# obc-v2_CM4-M2.net
KiCad netlist of a schematic drawn in Altium Designer
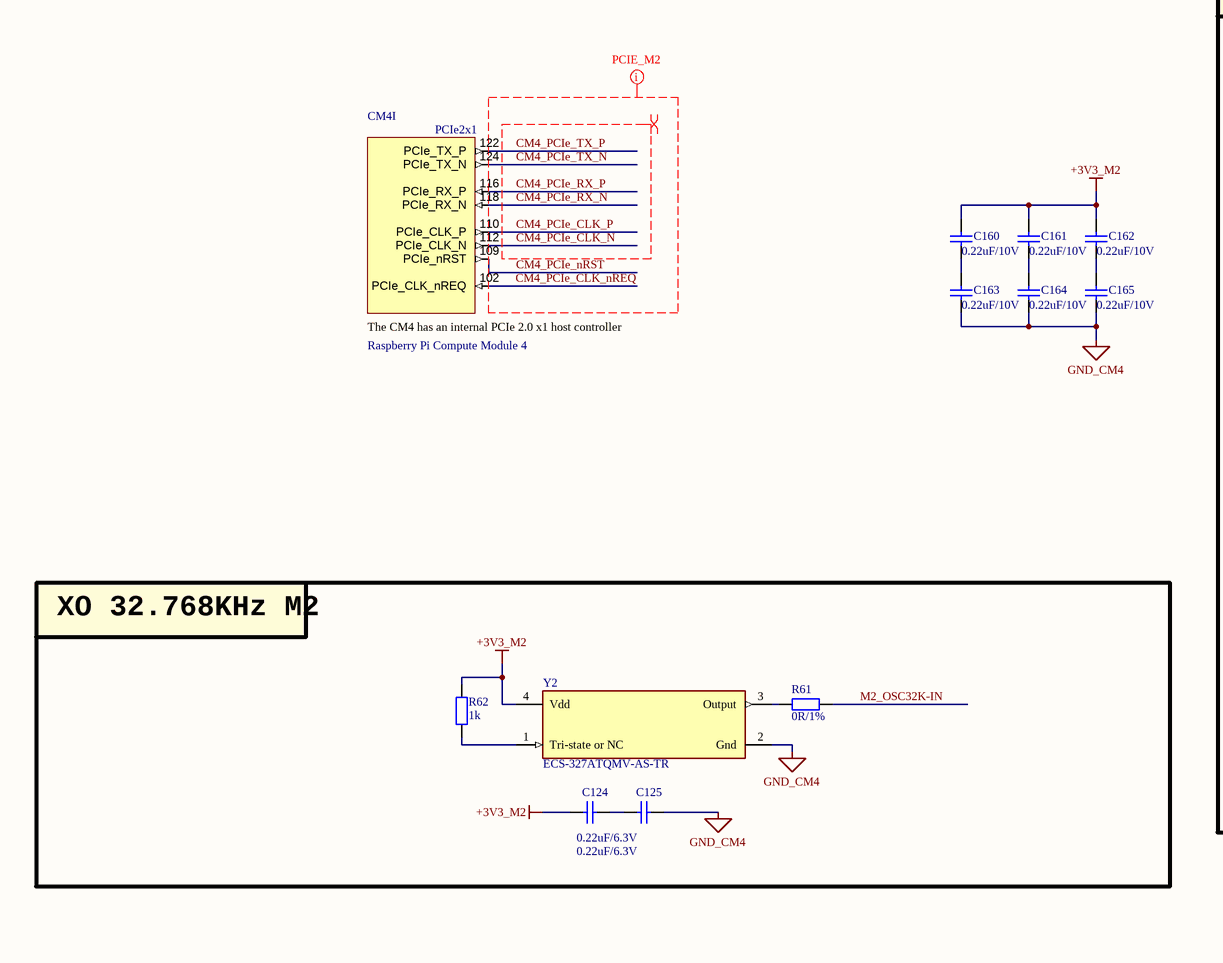
[diagram p0: obc-v2_CM4-M2.SchDoc, left]
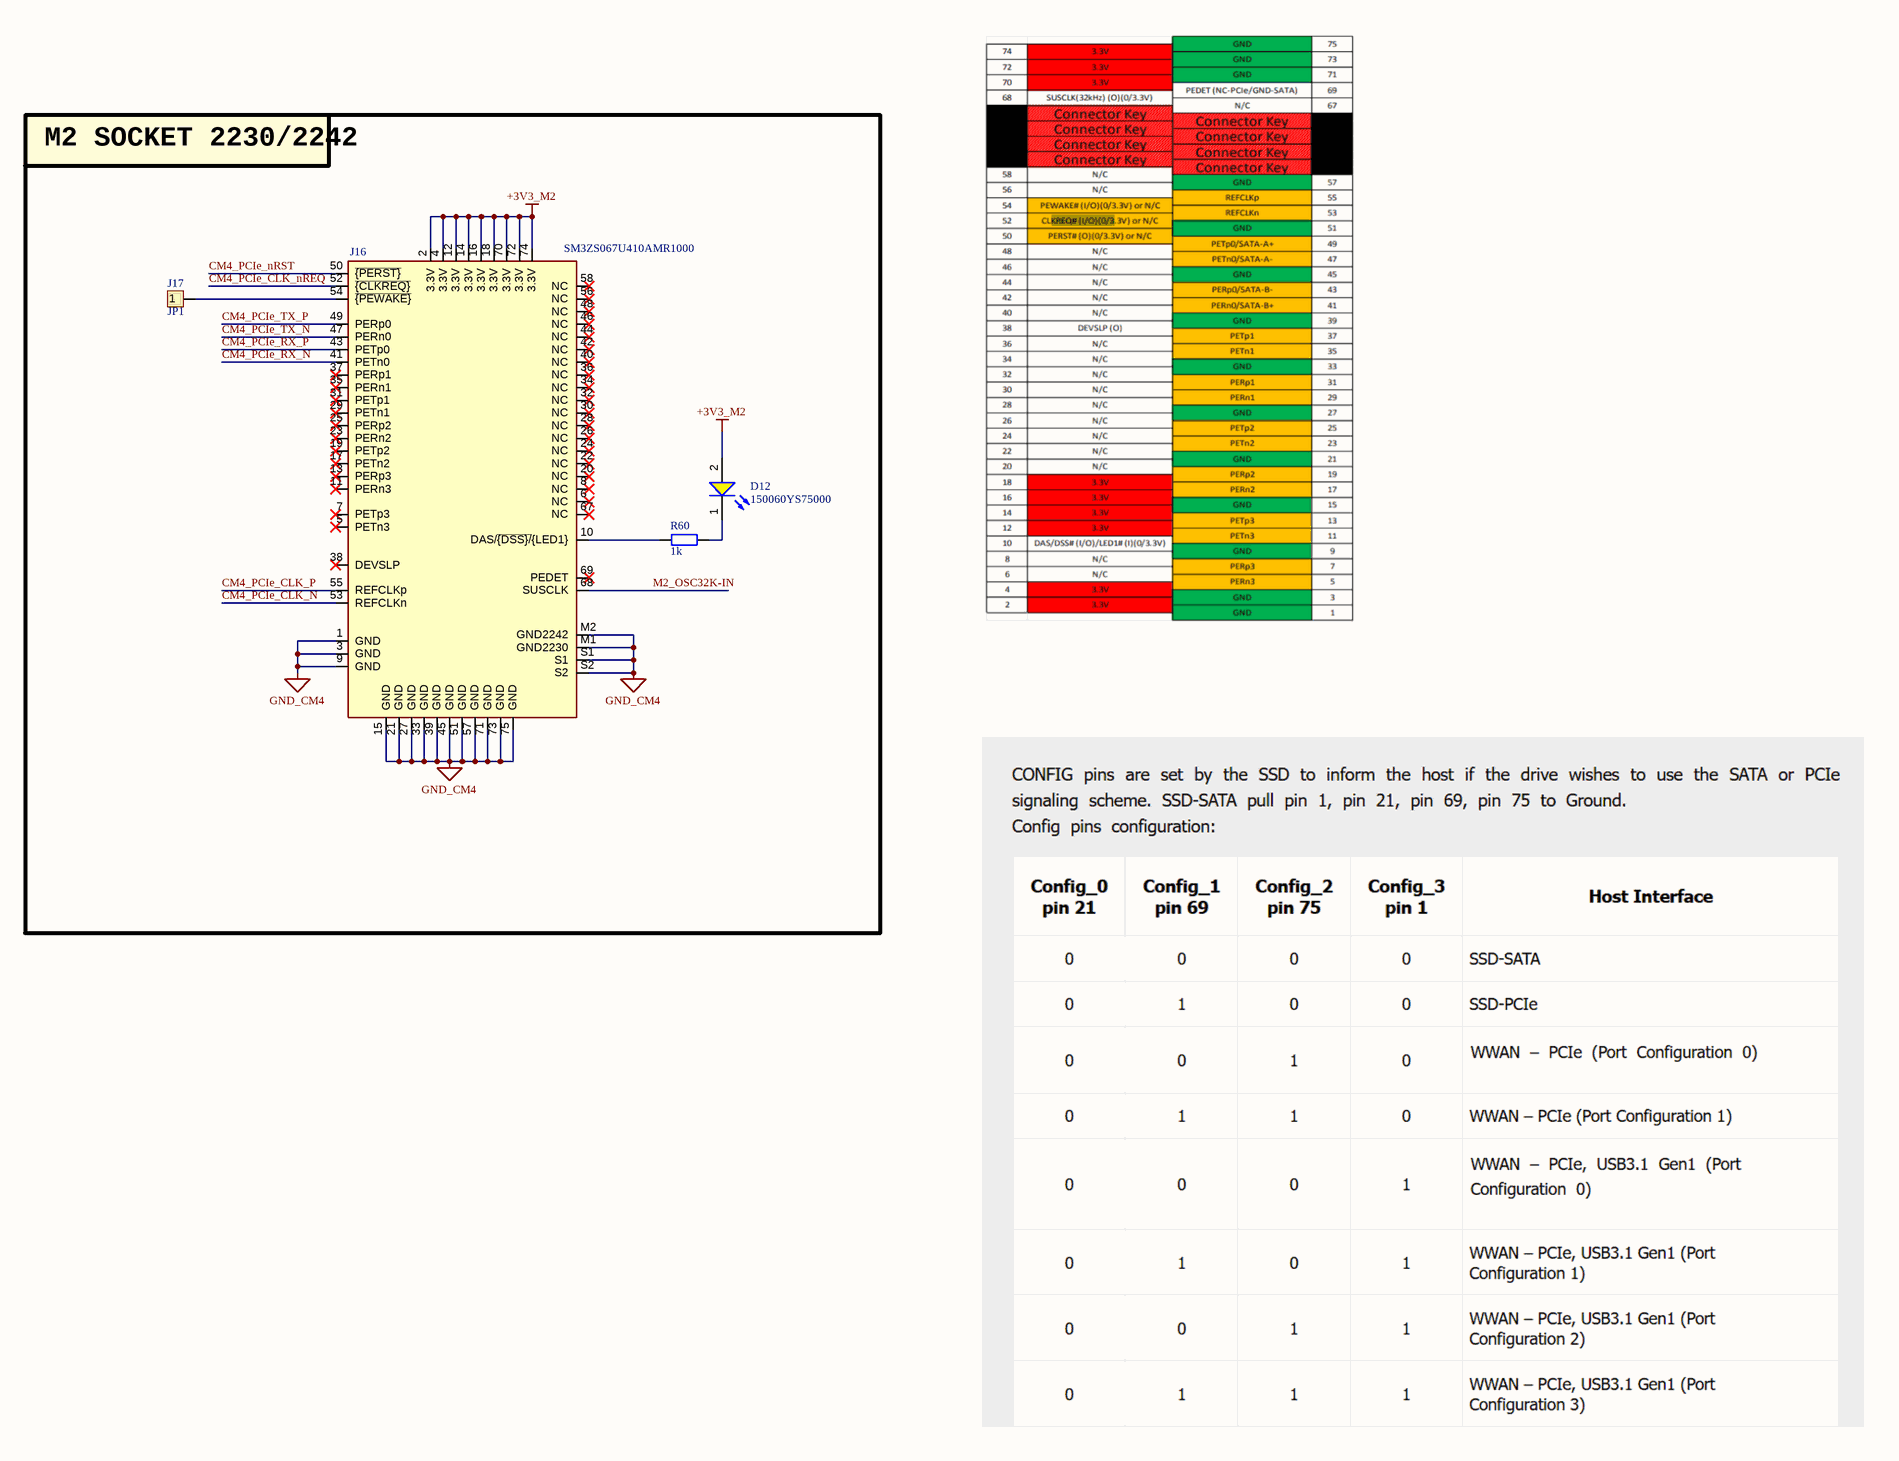
[diagram p1: obc-v2_CM4-M2.SchDoc, right]

(export (version "E")
  (design (tool "Eeschema 10.0.6"))
  (components
    (comp (ref "C124")
      (value "0.22uF/6.3V")
      (footprint "CAP_C_1005X60")
      (description "CAPC")
      (libsource (lib "Altium_Lib_by_KhueNguyenCreator") (part "Tu 0402 33nF 10V"))
    )
    (comp (ref "C125")
      (value "0.22uF/6.3V")
      (footprint "CAP_C_1005X60")
      (description "CAPC")
      (libsource (lib "Altium_Lib_by_KhueNguyenCreator") (part "Tu 0402 33nF 10V"))
    )
    (comp (ref "C160")
      (value "0.22uF/10V")
      (footprint "CAP_C_1005X60")
      (description "CAPC")
      (libsource (lib "Altium_Lib_by_KhueNguyenCreator") (part "Tu 0402 33nF 10V"))
    )
    (comp (ref "C161")
      (value "0.22uF/10V")
      (footprint "CAP_C_1005X60")
      (description "CAPC")
      (libsource (lib "Altium_Lib_by_KhueNguyenCreator") (part "Tu 0402 33nF 10V"))
    )
    (comp (ref "C162")
      (value "0.22uF/10V")
      (footprint "CAP_C_1005X60")
      (description "CAPC")
      (libsource (lib "Altium_Lib_by_KhueNguyenCreator") (part "Tu 0402 33nF 10V"))
    )
    (comp (ref "C163")
      (value "0.22uF/10V")
      (footprint "CAP_C_1005X60")
      (description "CAPC")
      (libsource (lib "Altium_Lib_by_KhueNguyenCreator") (part "Tu 0402 33nF 10V"))
    )
    (comp (ref "C164")
      (value "0.22uF/10V")
      (footprint "CAP_C_1005X60")
      (description "CAPC")
      (libsource (lib "Altium_Lib_by_KhueNguyenCreator") (part "Tu 0402 33nF 10V"))
    )
    (comp (ref "C165")
      (value "0.22uF/10V")
      (footprint "CAP_C_1005X60")
      (description "CAPC")
      (libsource (lib "Altium_Lib_by_KhueNguyenCreator") (part "Tu 0402 33nF 10V"))
    )
    (comp (ref "CM4")
      (value "Raspberry Pi Compute Module 4")
      (footprint "CM4-DF40HC(3.0)-100DS-0.4v_3mm_1.5mm")
      (description "Raspberry Pi Compute Module 4 by Amornthep Phunsin")
      (libsource (lib "CM4") (part "CM4"))
    )
    (comp (ref "D12")
      (value "150060YS75000")
      (footprint "WL-SMCW_0603_150060xx75000")
      (description "LED YELLOW CLEAR 0603 SMD")
      (libsource (lib "Altium Content Vault") (part "LED_Yellow_2A-1K"))
    )
    (comp (ref "J16")
      (value "SM3ZS067U410AMR1000")
      (footprint "M.2 M Key socket")
      (fields (field (name "Comment") "Bus_M.2_Socket_M"))
      (libsource (lib "CM5_GPIO") (part "Bus_M.2_Socket_M"))
    )
    (comp (ref "J17")
      (value "JP1")
      (footprint "JP1-D1T")
      (description "WR-PHD 2.54 mm Angled Socket Header")
      (fields
        (field (name "MANUFACTURER") "Würth Elektronik eiSos GmbH")
        (field (name "PARTNO") "613002143121")
        (field (name "CREATED BY") "Karrer Zheng")
      )
      (libsource (lib "TechMT.VN_Lib_Project v2") (part "JP1"))
    )
    (comp (ref "R60")
      (value "1k")
      (footprint "RES_C_1608X60")
      (description "RES")
      (libsource (lib "Altium_Lib_by_KhueNguyenCreator") (part "Tro 0603 1% 10k"))
    )
    (comp (ref "R61")
      (value "0R/1%")
      (footprint "RES_C_1608X60")
      (description "RES")
      (libsource (lib "Altium_Lib_by_KhueNguyenCreator") (part "Tro 0603 1% 10k"))
    )
    (comp (ref "R62")
      (value "1k")
      (footprint "RES_C_1608X60")
      (description "RES")
      (libsource (lib "Altium_Lib_by_KhueNguyenCreator") (part "Tro 0603 1% 10k"))
    )
    (comp (ref "Y2")
      (value "ECS-327ATQMV-AS-TR")
      (footprint "FP-327ATQMV-MFG")
      (description "XTAL OSC XO 32.7680KHZ CMOS SMD")
      (libsource (lib "Altium Content Vault") (part "48575ee33648fc99c8f9879a7ebcfb2"))
    )
  )
  (nets
    (net (code "1") (name "+3V3_M2") (class "Default")
      (node (ref "C124") (pin "1") (pinfunction "1_1") (pintype "passive"))
      (node (ref "C160") (pin "1") (pinfunction "1_1") (pintype "passive"))
      (node (ref "C161") (pin "1") (pinfunction "1_1") (pintype "passive"))
      (node (ref "C162") (pin "1") (pinfunction "1_1") (pintype "passive"))
      (node (ref "D12") (pin "2") (pinfunction "A_2") (pintype "passive"))
      (node (ref "J16") (pin "12") (pinfunction "3.3V_12") (pintype "passive"))
      (node (ref "J16") (pin "14") (pinfunction "3.3V_14") (pintype "passive"))
      (node (ref "J16") (pin "16") (pinfunction "3.3V_16") (pintype "passive"))
      (node (ref "J16") (pin "18") (pinfunction "3.3V_18") (pintype "passive"))
      (node (ref "J16") (pin "2") (pinfunction "3.3V_2") (pintype "passive"))
      (node (ref "J16") (pin "4") (pinfunction "3.3V_4") (pintype "passive"))
      (node (ref "J16") (pin "70") (pinfunction "3.3V_70") (pintype "passive"))
      (node (ref "J16") (pin "72") (pinfunction "3.3V_72") (pintype "passive"))
      (node (ref "J16") (pin "74") (pinfunction "3.3V_74") (pintype "passive"))
      (node (ref "R62") (pin "1") (pinfunction "1_1") (pintype "passive"))
      (node (ref "Y2") (pin "4") (pinfunction "Vdd_4") (pintype "power_in"))
    )
    (net (code "2") (name "/CM4_PCIe_CLK_N") (class "Default")
      (node (ref "CM4") (pin "112") (pinfunction "PCIe_CLK_N_112") (pintype "output"))
      (node (ref "J16") (pin "53") (pinfunction "REFCLKn_53") (pintype "passive"))
    )
    (net (code "3") (name "/CM4_PCIe_CLK_P") (class "Default")
      (node (ref "CM4") (pin "110") (pinfunction "PCIe_CLK_P_110") (pintype "output"))
      (node (ref "J16") (pin "55") (pinfunction "REFCLKp_55") (pintype "passive"))
    )
    (net (code "4") (name "/CM4_PCIe_CLK_nREQ") (class "Default")
      (node (ref "CM4") (pin "102") (pinfunction "PCIe_CLK_nREQ_102") (pintype "input"))
      (node (ref "J16") (pin "52") (pinfunction "~{{CLKREQ}}_52") (pintype "passive"))
    )
    (net (code "5") (name "/CM4_PCIe_RX_N") (class "Default")
      (node (ref "CM4") (pin "118") (pinfunction "PCIe_RX_N_118") (pintype "input"))
      (node (ref "J16") (pin "41") (pinfunction "PETn0_41") (pintype "passive"))
    )
    (net (code "6") (name "/CM4_PCIe_RX_P") (class "Default")
      (node (ref "CM4") (pin "116") (pinfunction "PCIe_RX_P_116") (pintype "input"))
      (node (ref "J16") (pin "43") (pinfunction "PETp0_43") (pintype "passive"))
    )
    (net (code "7") (name "/CM4_PCIe_TX_N") (class "Default")
      (node (ref "CM4") (pin "124") (pinfunction "PCIe_TX_N_124") (pintype "output"))
      (node (ref "J16") (pin "47") (pinfunction "PERn0_47") (pintype "passive"))
    )
    (net (code "8") (name "/CM4_PCIe_TX_P") (class "Default")
      (node (ref "CM4") (pin "122") (pinfunction "PCIe_TX_P_122") (pintype "output"))
      (node (ref "J16") (pin "49") (pinfunction "PERp0_49") (pintype "passive"))
    )
    (net (code "9") (name "/CM4_PCIe_nRST") (class "Default")
      (node (ref "CM4") (pin "109") (pinfunction "PCIe_nRST_109") (pintype "output"))
      (node (ref "J16") (pin "50") (pinfunction "~{{PERST}}_50") (pintype "passive"))
    )
    (net (code "10") (name "/M2_OSC32K-IN") (class "Default")
      (node (ref "J16") (pin "68") (pinfunction "SUSCLK_68") (pintype "passive"))
      (node (ref "R61") (pin "1") (pinfunction "1_1") (pintype "passive"))
    )
    (net (code "11") (name "GND_CM4") (class "Default")
      (node (ref "C125") (pin "2") (pinfunction "2_2") (pintype "passive"))
      (node (ref "C163") (pin "2") (pinfunction "2_2") (pintype "passive"))
      (node (ref "C164") (pin "2") (pinfunction "2_2") (pintype "passive"))
      (node (ref "C165") (pin "2") (pinfunction "2_2") (pintype "passive"))
      (node (ref "J16") (pin "1") (pinfunction "GND_1") (pintype "passive"))
      (node (ref "J16") (pin "15") (pinfunction "GND_15") (pintype "passive"))
      (node (ref "J16") (pin "21") (pinfunction "GND_21") (pintype "passive"))
      (node (ref "J16") (pin "27") (pinfunction "GND_27") (pintype "passive"))
      (node (ref "J16") (pin "3") (pinfunction "GND_3") (pintype "passive"))
      (node (ref "J16") (pin "33") (pinfunction "GND_33") (pintype "passive"))
      (node (ref "J16") (pin "39") (pinfunction "GND_39") (pintype "passive"))
      (node (ref "J16") (pin "45") (pinfunction "GND_45") (pintype "passive"))
      (node (ref "J16") (pin "51") (pinfunction "GND_51") (pintype "passive"))
      (node (ref "J16") (pin "57") (pinfunction "GND_57") (pintype "passive"))
      (node (ref "J16") (pin "71") (pinfunction "GND_71") (pintype "passive"))
      (node (ref "J16") (pin "73") (pinfunction "GND_73") (pintype "passive"))
      (node (ref "J16") (pin "75") (pinfunction "GND_75") (pintype "passive"))
      (node (ref "J16") (pin "9") (pinfunction "GND_9") (pintype "passive"))
      (node (ref "J16") (pin "M1") (pinfunction "GND2230_M1") (pintype "passive"))
      (node (ref "J16") (pin "M2") (pinfunction "GND2242_M2") (pintype "passive"))
      (node (ref "J16") (pin "S1") (pinfunction "S1_S1") (pintype "passive"))
      (node (ref "J16") (pin "S2") (pinfunction "S2_S2") (pintype "passive"))
      (node (ref "Y2") (pin "2") (pinfunction "Gnd_2") (pintype "power_in"))
    )
    (net (code "12") (name "Net-(C124-Pad2)") (class "Default")
      (node (ref "C124") (pin "2") (pinfunction "2_2") (pintype "passive"))
      (node (ref "C125") (pin "1") (pinfunction "1_1") (pintype "passive"))
    )
    (net (code "13") (name "Net-(C160-Pad2)") (class "Default")
      (node (ref "C160") (pin "2") (pinfunction "2_2") (pintype "passive"))
      (node (ref "C163") (pin "1") (pinfunction "1_1") (pintype "passive"))
    )
    (net (code "14") (name "Net-(C161-Pad2)") (class "Default")
      (node (ref "C161") (pin "2") (pinfunction "2_2") (pintype "passive"))
      (node (ref "C164") (pin "1") (pinfunction "1_1") (pintype "passive"))
    )
    (net (code "15") (name "Net-(C162-Pad2)") (class "Default")
      (node (ref "C162") (pin "2") (pinfunction "2_2") (pintype "passive"))
      (node (ref "C165") (pin "1") (pinfunction "1_1") (pintype "passive"))
    )
    (net (code "16") (name "Net-(D12-K)") (class "Default")
      (node (ref "D12") (pin "1") (pinfunction "K_1") (pintype "passive"))
      (node (ref "R60") (pin "1") (pinfunction "1_1") (pintype "passive"))
    )
    (net (code "17") (name "Net-(J16-DAS{slash}~{{DSS}{slash}}{LED1})") (class "Default")
      (node (ref "J16") (pin "10") (pinfunction "DAS/~{{DSS}/}{LED1}_10") (pintype "passive"))
      (node (ref "R60") (pin "2") (pinfunction "2_2") (pintype "passive"))
    )
    (net (code "18") (name "Net-(J16-~{{PEWAKE}})") (class "Default")
      (node (ref "J16") (pin "54") (pinfunction "~{{PEWAKE}}_54") (pintype "passive"))
      (node (ref "J17") (pin "1") (pinfunction "1_1") (pintype "passive"))
    )
    (net (code "19") (name "Net-(Y2-Output)") (class "Default")
      (node (ref "R61") (pin "2") (pinfunction "2_2") (pintype "passive"))
      (node (ref "Y2") (pin "3") (pinfunction "Output_3") (pintype "output"))
    )
    (net (code "20") (name "Net-(Y2-Tri-state_or_NC)") (class "Default")
      (node (ref "R62") (pin "2") (pinfunction "2_2") (pintype "passive"))
      (node (ref "Y2") (pin "1") (pinfunction "Tri-state_or_NC_1") (pintype "input"))
    )
    (net (code "21") (name "unconnected-(J16-DEVSLP-Pad38)") (class "Default")
      (node (ref "J16") (pin "38") (pinfunction "DEVSLP_38") (pintype "passive+no_connect"))
    )
    (net (code "22") (name "unconnected-(J16-NC-Pad6)") (class "Default")
      (node (ref "J16") (pin "6") (pinfunction "NC_6") (pintype "passive+no_connect"))
    )
    (net (code "23") (name "unconnected-(J16-NC-Pad8)") (class "Default")
      (node (ref "J16") (pin "8") (pinfunction "NC_8") (pintype "passive+no_connect"))
    )
    (net (code "24") (name "unconnected-(J16-NC-Pad20)") (class "Default")
      (node (ref "J16") (pin "20") (pinfunction "NC_20") (pintype "passive+no_connect"))
    )
    (net (code "25") (name "unconnected-(J16-NC-Pad22)") (class "Default")
      (node (ref "J16") (pin "22") (pinfunction "NC_22") (pintype "passive+no_connect"))
    )
    (net (code "26") (name "unconnected-(J16-NC-Pad24)") (class "Default")
      (node (ref "J16") (pin "24") (pinfunction "NC_24") (pintype "passive+no_connect"))
    )
    (net (code "27") (name "unconnected-(J16-NC-Pad26)") (class "Default")
      (node (ref "J16") (pin "26") (pinfunction "NC_26") (pintype "passive+no_connect"))
    )
    (net (code "28") (name "unconnected-(J16-NC-Pad28)") (class "Default")
      (node (ref "J16") (pin "28") (pinfunction "NC_28") (pintype "passive+no_connect"))
    )
    (net (code "29") (name "unconnected-(J16-NC-Pad30)") (class "Default")
      (node (ref "J16") (pin "30") (pinfunction "NC_30") (pintype "passive+no_connect"))
    )
    (net (code "30") (name "unconnected-(J16-NC-Pad32)") (class "Default")
      (node (ref "J16") (pin "32") (pinfunction "NC_32") (pintype "passive+no_connect"))
    )
    (net (code "31") (name "unconnected-(J16-NC-Pad34)") (class "Default")
      (node (ref "J16") (pin "34") (pinfunction "NC_34") (pintype "passive+no_connect"))
    )
    (net (code "32") (name "unconnected-(J16-NC-Pad36)") (class "Default")
      (node (ref "J16") (pin "36") (pinfunction "NC_36") (pintype "passive+no_connect"))
    )
    (net (code "33") (name "unconnected-(J16-NC-Pad40)") (class "Default")
      (node (ref "J16") (pin "40") (pinfunction "NC_40") (pintype "passive+no_connect"))
    )
    (net (code "34") (name "unconnected-(J16-NC-Pad42)") (class "Default")
      (node (ref "J16") (pin "42") (pinfunction "NC_42") (pintype "passive+no_connect"))
    )
    (net (code "35") (name "unconnected-(J16-NC-Pad44)") (class "Default")
      (node (ref "J16") (pin "44") (pinfunction "NC_44") (pintype "passive+no_connect"))
    )
    (net (code "36") (name "unconnected-(J16-NC-Pad46)") (class "Default")
      (node (ref "J16") (pin "46") (pinfunction "NC_46") (pintype "passive+no_connect"))
    )
    (net (code "37") (name "unconnected-(J16-NC-Pad48)") (class "Default")
      (node (ref "J16") (pin "48") (pinfunction "NC_48") (pintype "passive+no_connect"))
    )
    (net (code "38") (name "unconnected-(J16-NC-Pad56)") (class "Default")
      (node (ref "J16") (pin "56") (pinfunction "NC_56") (pintype "passive+no_connect"))
    )
    (net (code "39") (name "unconnected-(J16-NC-Pad58)") (class "Default")
      (node (ref "J16") (pin "58") (pinfunction "NC_58") (pintype "passive+no_connect"))
    )
    (net (code "40") (name "unconnected-(J16-NC-Pad67)") (class "Default")
      (node (ref "J16") (pin "67") (pinfunction "NC_67") (pintype "passive+no_connect"))
    )
    (net (code "41") (name "unconnected-(J16-PEDET-Pad69)") (class "Default")
      (node (ref "J16") (pin "69") (pinfunction "PEDET_69") (pintype "passive+no_connect"))
    )
    (net (code "42") (name "unconnected-(J16-PERn1-Pad35)") (class "Default")
      (node (ref "J16") (pin "35") (pinfunction "PERn1_35") (pintype "passive+no_connect"))
    )
    (net (code "43") (name "unconnected-(J16-PERn2-Pad23)") (class "Default")
      (node (ref "J16") (pin "23") (pinfunction "PERn2_23") (pintype "passive+no_connect"))
    )
    (net (code "44") (name "unconnected-(J16-PERn3-Pad11)") (class "Default")
      (node (ref "J16") (pin "11") (pinfunction "PERn3_11") (pintype "passive+no_connect"))
    )
    (net (code "45") (name "unconnected-(J16-PERp1-Pad37)") (class "Default")
      (node (ref "J16") (pin "37") (pinfunction "PERp1_37") (pintype "passive+no_connect"))
    )
    (net (code "46") (name "unconnected-(J16-PERp2-Pad25)") (class "Default")
      (node (ref "J16") (pin "25") (pinfunction "PERp2_25") (pintype "passive+no_connect"))
    )
    (net (code "47") (name "unconnected-(J16-PERp3-Pad13)") (class "Default")
      (node (ref "J16") (pin "13") (pinfunction "PERp3_13") (pintype "passive+no_connect"))
    )
    (net (code "48") (name "unconnected-(J16-PETn1-Pad29)") (class "Default")
      (node (ref "J16") (pin "29") (pinfunction "PETn1_29") (pintype "passive+no_connect"))
    )
    (net (code "49") (name "unconnected-(J16-PETn2-Pad17)") (class "Default")
      (node (ref "J16") (pin "17") (pinfunction "PETn2_17") (pintype "passive+no_connect"))
    )
    (net (code "50") (name "unconnected-(J16-PETn3-Pad5)") (class "Default")
      (node (ref "J16") (pin "5") (pinfunction "PETn3_5") (pintype "passive+no_connect"))
    )
    (net (code "51") (name "unconnected-(J16-PETp1-Pad31)") (class "Default")
      (node (ref "J16") (pin "31") (pinfunction "PETp1_31") (pintype "passive+no_connect"))
    )
    (net (code "52") (name "unconnected-(J16-PETp2-Pad19)") (class "Default")
      (node (ref "J16") (pin "19") (pinfunction "PETp2_19") (pintype "passive+no_connect"))
    )
    (net (code "53") (name "unconnected-(J16-PETp3-Pad7)") (class "Default")
      (node (ref "J16") (pin "7") (pinfunction "PETp3_7") (pintype "passive+no_connect"))
    )
  )
)
